# GPRS.net
KiCad netlist of a schematic drawn in Altium Designer
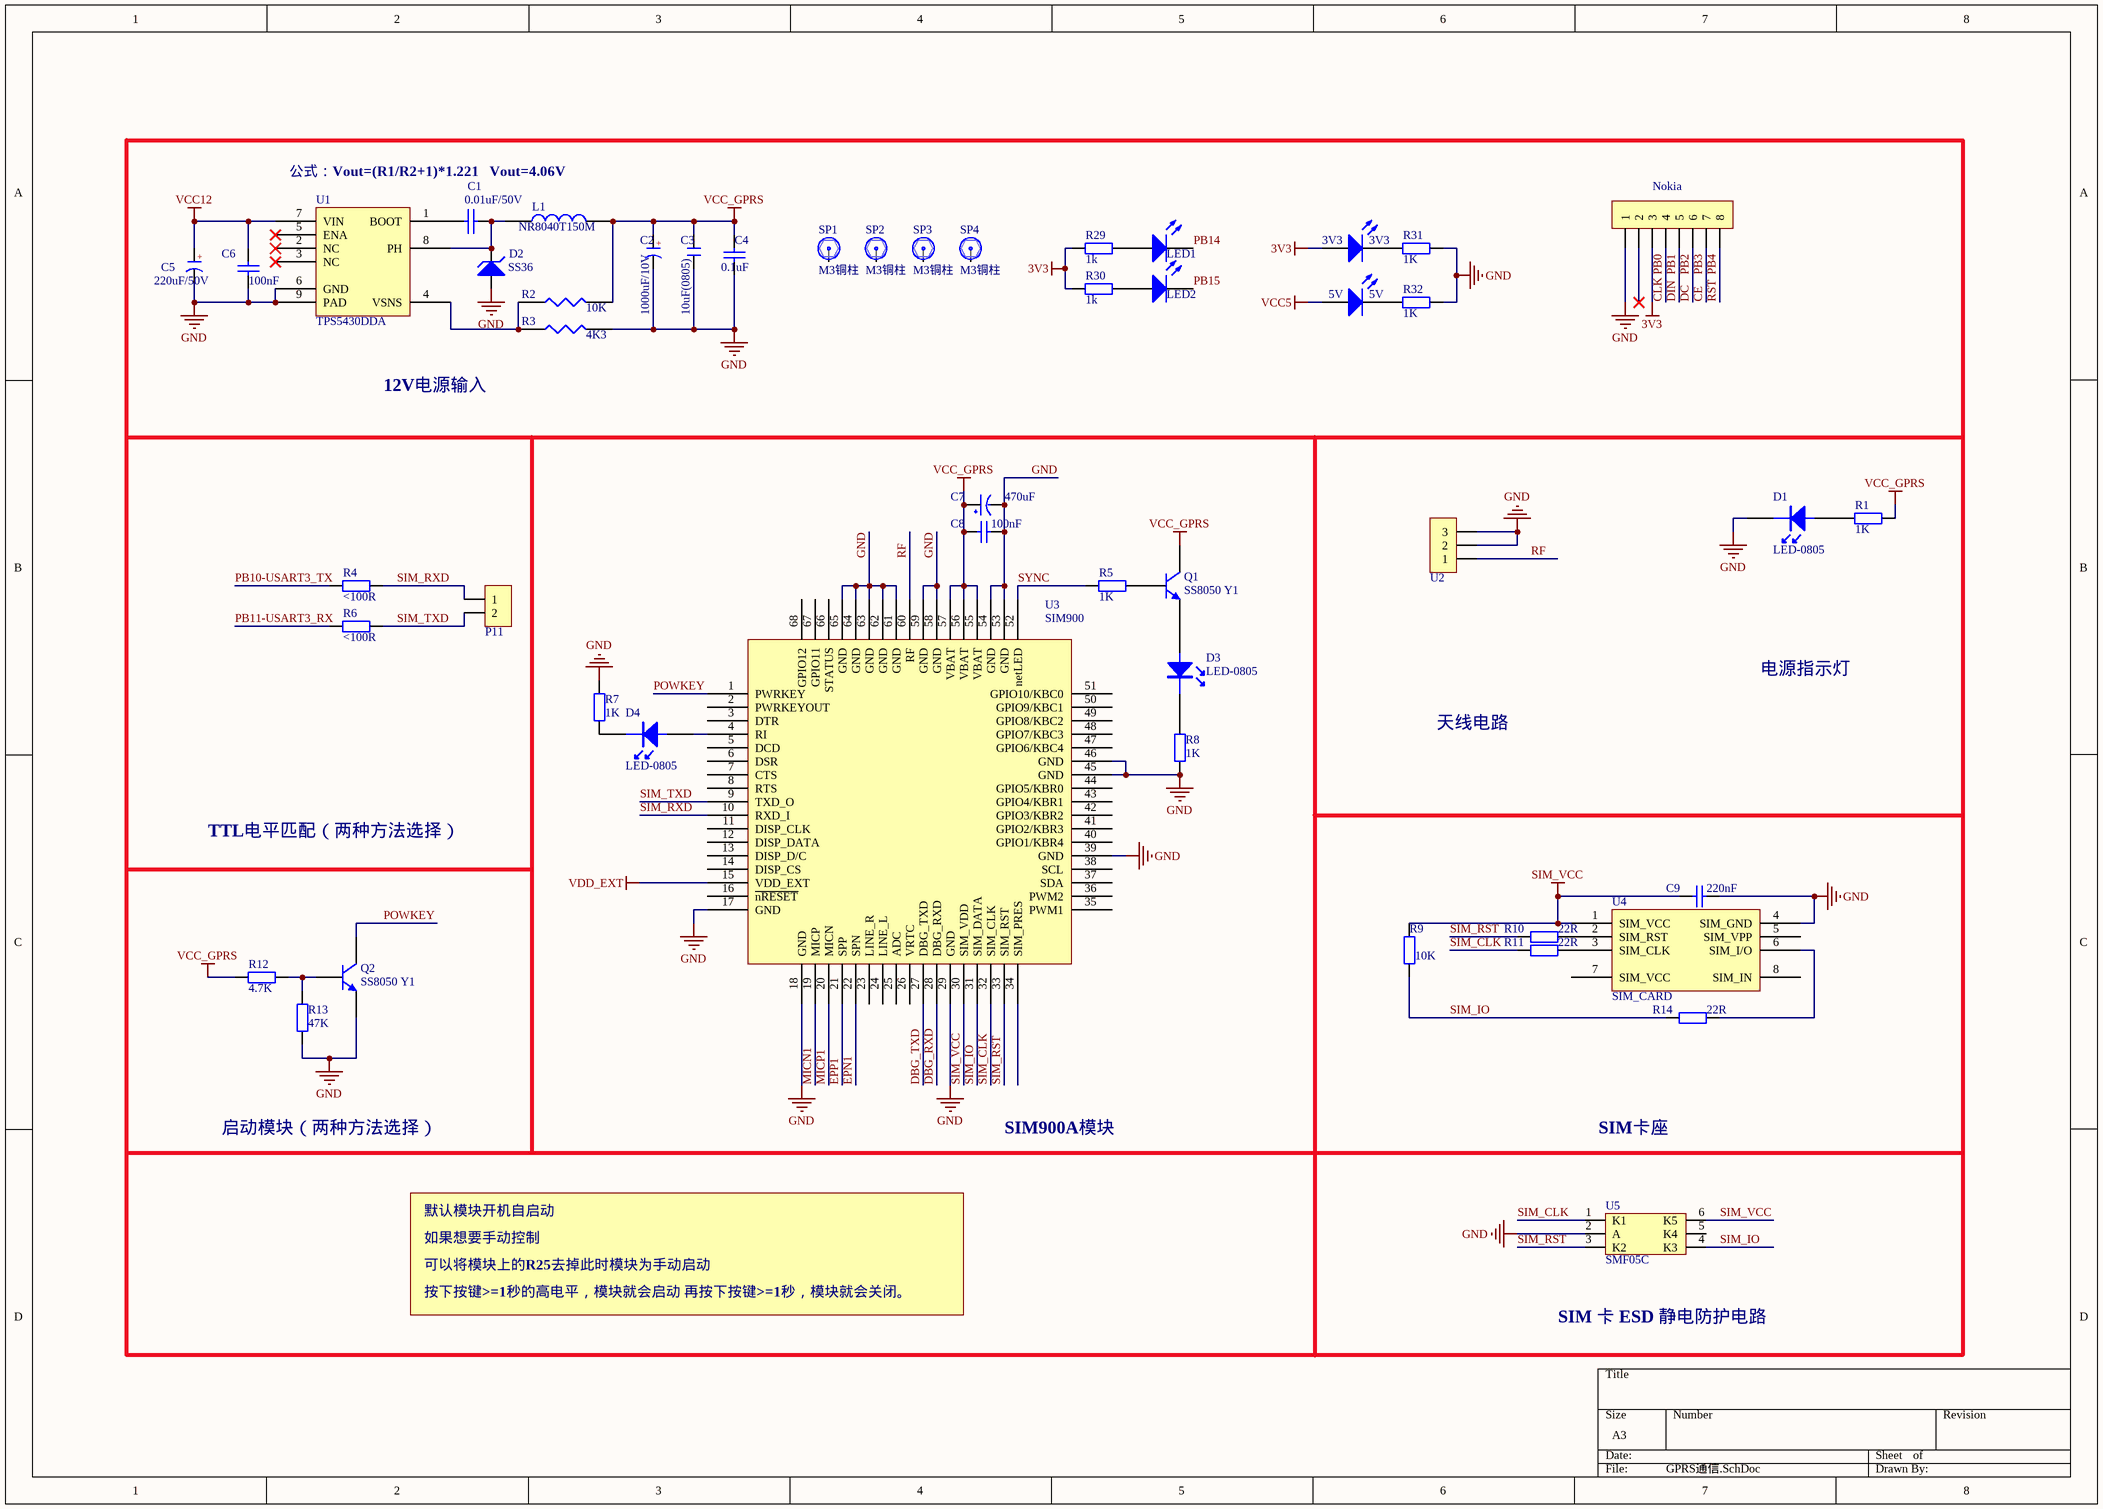
[diagram p0: GPRS通信.SchDoc]

(export (version "E")
  (design (tool "Eeschema 10.0.6"))
  (components
    (comp (ref "3V3")
      (value "3V3")
      (footprint "LED 0805G")
      (description "Typical INFRARED GaAs LED")
      (fields (field (name "PUBLISHER") "Altium Limited"))
      (libsource (lib "PCB_Project") (part "LED0"))
    )
    (comp (ref "5V")
      (value "5V")
      (footprint "LED 0805G")
      (description "Typical INFRARED GaAs LED")
      (fields (field (name "PUBLISHER") "Altium Limited"))
      (libsource (lib "PCB_Project") (part "LED0"))
    )
    (comp (ref "C1")
      (value "0.01uF/50V")
      (footprint "LC-0603_C")
      (description "Capacitor")
      (libsource (lib "*") (part "CAP"))
    )
    (comp (ref "C2")
      (value "1000uF/10V")
      (footprint "CAP 5.0*10*20 - BK")
      (description "直插电解电容")
      (fields (field (name "版权归属") "源创客"))
      (libsource (lib "3.1   - 电阻-电容-电感") (part "C-CAP"))
    )
    (comp (ref "C3")
      (value "10uF(0805)")
      (footprint "C 0805_L")
      (description "无极性贴片电容")
      (fields (field (name "版权归属") "源创客"))
      (libsource (lib "3.1   - 电阻-电容-电感") (part "C"))
    )
    (comp (ref "C4")
      (value "0.1uF")
      (footprint "LC-0603_C")
      (description "贴片电容")
      (libsource (lib "Miscellaneous Devices LC") (part "0603 1.0pF (010) 0.25pF 50V"))
    )
    (comp (ref "C5")
      (value "220uF/50V")
      (footprint "CAP 3.5*8*11.5 - BK")
      (description "直插电解电容")
      (fields (field (name "版权归属") "源创客"))
      (libsource (lib "3.1   - 电阻-电容-电感") (part "C-CAP"))
    )
    (comp (ref "C6")
      (value "100nF")
      (footprint "LC-0603_C")
      (description "贴片电容")
      (libsource (lib "Miscellaneous Devices LC") (part "0603 1uF (105) 10% 50V"))
    )
    (comp (ref "C7")
      (value "470uF")
      (footprint "CM E(8*10.2)")
      (libsource (lib "Explorer STM32F407封装库") (part "CAP"))
    )
    (comp (ref "C8")
      (value "100nF")
      (footprint "LC-0603_C")
      (description "贴片电容")
      (libsource (lib "Miscellaneous Devices LC") (part "0603 1uF (105) 10% 50V"))
    )
    (comp (ref "C9")
      (value "220nF")
      (footprint "LC-0603_C")
      (description "贴片电容")
      (libsource (lib "Miscellaneous Devices LC") (part "0603 1uF (105) 10% 50V"))
    )
    (comp (ref "D1")
      (value "LED-0805")
      (footprint "LED 0805G")
      (description "贴片LED")
      (libsource (lib "CD's_LIB_2018") (part "LED_SMD"))
    )
    (comp (ref "D2")
      (value "SS36")
      (footprint "D1812")
      (description "Zener Diode")
      (libsource (lib "*") (part "SS36"))
    )
    (comp (ref "D3")
      (value "LED-0805")
      (footprint "LED 0805G")
      (description "贴片LED")
      (libsource (lib "CD's_LIB_2018") (part "LED_SMD"))
    )
    (comp (ref "D4")
      (value "LED-0805")
      (footprint "LED 0805G")
      (description "贴片LED")
      (libsource (lib "CD's_LIB_2018") (part "LED_SMD"))
    )
    (comp (ref "L1") (value "NR8040T150M") (footprint "NR8040") (libsource (lib "*") (part "INDUCTOR")))
    (comp (ref "LED1")
      (value "~")
      (footprint "LED 0805G")
      (description "Typical INFRARED GaAs LED")
      (fields (field (name "PUBLISHER") "Altium Limited"))
      (libsource (lib "PCB_Project") (part "LED0"))
    )
    (comp (ref "LED2")
      (value "~")
      (footprint "LED 0805G")
      (description "Typical INFRARED GaAs LED")
      (fields (field (name "PUBLISHER") "Altium Limited"))
      (libsource (lib "PCB_Project") (part "LED0"))
    )
    (comp (ref "Nokia")
      (value "HDR-1X8")
      (footprint "HDR2.54-M-LI-8P")
      (description "8P接插件")
      (fields (field (name "版权归属") "源创客"))
      (libsource (lib "4.5   - 接插件-脚距2.54") (part "Header 8"))
    )
    (comp (ref "P11")
      (value "HDR-1X2")
      (footprint "HDR2.54-LI-2P")
      (description "2P接插件")
      (fields (field (name "版权归属") "源创客"))
      (libsource (lib "4.5   - 接插件-脚距2.54") (part "Header 2"))
    )
    (comp (ref "Q1")
      (value "SS8050 Y1")
      (footprint "LC-SOT-23(SOT-23-3)")
      (description "三极管")
      (libsource (lib "Miscellaneous Devices LC") (part "SOT-23 SS8050 Y1"))
    )
    (comp (ref "Q2")
      (value "SS8050 Y1")
      (footprint "LC-SOT-23(SOT-23-3)")
      (description "三极管")
      (libsource (lib "Miscellaneous Devices LC") (part "SOT-23 SS8050 Y1"))
    )
    (comp (ref "R1")
      (value "1K")
      (footprint "LC-0603_R")
      (description "贴片电阻")
      (libsource (lib "") (part "0603 2KΩ (2001) 1%_1"))
    )
    (comp (ref "R2") (value "10K") (footprint "LC-0603_R") (libsource (lib "*") (part "RES1")))
    (comp (ref "R3") (value "4K3") (footprint "LC-0603_R") (libsource (lib "*") (part "RES1")))
    (comp (ref "R4")
      (value "<100R")
      (footprint "LC-0603_R")
      (description "贴片电阻")
      (libsource (lib "Miscellaneous Devices LC") (part "0603 2KΩ (2001) 1%"))
    )
    (comp (ref "R5")
      (value "1K")
      (footprint "LC-0603_R")
      (description "贴片电阻")
      (libsource (lib "") (part "0603 2KΩ (2001) 1%_1"))
    )
    (comp (ref "R6")
      (value "<100R")
      (footprint "LC-0603_R")
      (description "贴片电阻")
      (libsource (lib "Miscellaneous Devices LC") (part "0603 2KΩ (2001) 1%"))
    )
    (comp (ref "R7")
      (value "1K")
      (footprint "LC-0603_R")
      (description "贴片电阻")
      (libsource (lib "") (part "0603 2KΩ (2001) 1%_2"))
    )
    (comp (ref "R8")
      (value "1K")
      (footprint "LC-0603_R")
      (description "贴片电阻")
      (libsource (lib "") (part "0603 2KΩ (2001) 1%_3"))
    )
    (comp (ref "R9")
      (value "10K")
      (footprint "LC-0603_R")
      (description "贴片电阻")
      (libsource (lib "") (part "0603 2KΩ (2001) 1%_2"))
    )
    (comp (ref "R10")
      (value "22R")
      (footprint "LC-0603_R")
      (description "贴片电阻")
      (libsource (lib "") (part "0603 2KΩ (2001) 1%_1"))
    )
    (comp (ref "R11")
      (value "22R")
      (footprint "LC-0603_R")
      (description "贴片电阻")
      (libsource (lib "") (part "0603 2KΩ (2001) 1%_1"))
    )
    (comp (ref "R12")
      (value "4.7K")
      (footprint "LC-0603_R")
      (description "贴片电阻")
      (libsource (lib "Miscellaneous Devices LC") (part "0603 2KΩ (2001) 1%"))
    )
    (comp (ref "R13")
      (value "47K")
      (footprint "LC-0603_R")
      (description "贴片电阻")
      (libsource (lib "") (part "0603 2KΩ (2001) 1%_2"))
    )
    (comp (ref "R14")
      (value "22R")
      (footprint "LC-0603_R")
      (description "贴片电阻")
      (libsource (lib "") (part "0603 2KΩ (2001) 1%_1"))
    )
    (comp (ref "R29")
      (value "1k")
      (footprint "LC-0603_R")
      (description "贴片电阻")
      (fields (field (name "PUBLISHER") "Altium Limited"))
      (libsource (lib "liu_2016") (part "Res1"))
    )
    (comp (ref "R30")
      (value "1k")
      (footprint "LC-0603_R")
      (description "贴片电阻")
      (fields (field (name "PUBLISHER") "Altium Limited"))
      (libsource (lib "liu_2016") (part "Res1"))
    )
    (comp (ref "R31")
      (value "1K")
      (footprint "LC-0603_R")
      (description "贴片电阻")
      (libsource (lib "Miscellaneous Devices LC") (part "0603 1.1KΩ (1101) 1%"))
    )
    (comp (ref "R32")
      (value "1K")
      (footprint "LC-0603_R")
      (description "贴片电阻")
      (libsource (lib "Miscellaneous Devices LC") (part "0603 1.1KΩ (1101) 1%"))
    )
    (comp (ref "SP1")
      (value "M3铜柱")
      (footprint "M3x10+6_N")
      (description "铜柱")
      (fields (field (name "版权归属") "源创客"))
      (libsource (lib "15.1 - 未分类器件") (part "铜柱加头大焊盘"))
    )
    (comp (ref "SP2")
      (value "M3铜柱")
      (footprint "M3x10+6_N")
      (description "铜柱")
      (fields (field (name "版权归属") "源创客"))
      (libsource (lib "15.1 - 未分类器件") (part "铜柱加头大焊盘"))
    )
    (comp (ref "SP3")
      (value "M3铜柱")
      (footprint "M3x10+6_N")
      (description "铜柱")
      (fields (field (name "版权归属") "源创客"))
      (libsource (lib "15.1 - 未分类器件") (part "铜柱加头大焊盘"))
    )
    (comp (ref "SP4")
      (value "M3铜柱")
      (footprint "M3x10+6_N")
      (description "铜柱")
      (fields (field (name "版权归属") "源创客"))
      (libsource (lib "15.1 - 未分类器件") (part "铜柱加头大焊盘"))
    )
    (comp (ref "U1") (value "TPS5430DDA") (footprint "SO-G8") (libsource (lib "*") (part "TPS5430DDA")))
    (comp (ref "U2")
      (value "HDR-1X3")
      (footprint "SMA-KE-LI")
      (description "3P接插件")
      (fields (field (name "版权归属") "源创客"))
      (libsource (lib "4.5   - 接插件-脚距2.54") (part "Header 3"))
    )
    (comp (ref "U3") (value "SIM900") (footprint "GSM_900A") (libsource (lib "ATK-SIM900A") (part "SIM900")))
    (comp (ref "U4")
      (value "SIM_CARD")
      (footprint "MICRO SIM6")
      (description "SIM中卡卡槽")
      (libsource (lib "liu_2016") (part "SIM_CARD"))
    )
    (comp (ref "U5")
      (value "SMF05C")
      (footprint "SOT-363")
      (description "TVS")
      (libsource (lib "ATK-SIM900A GSM模块封装库") (part "SMF05C"))
    )
  )
  (nets
    (net (code "1") (name "/CE") (class "Default")
      (node (ref "Nokia") (pin "7") (pinfunction "7_7") (pintype "passive"))
    )
    (net (code "2") (name "/CLK") (class "Default")
      (node (ref "Nokia") (pin "4") (pinfunction "4_4") (pintype "passive"))
    )
    (net (code "3") (name "/DBG_RXD") (class "Default")
      (node (ref "U3") (pin "28") (pinfunction "DBG_RXD_28") (pintype "passive"))
    )
    (net (code "4") (name "/DBG_TXD") (class "Default")
      (node (ref "U3") (pin "27") (pinfunction "DBG_TXD_27") (pintype "passive"))
    )
    (net (code "5") (name "/DC") (class "Default")
      (node (ref "Nokia") (pin "6") (pinfunction "6_6") (pintype "passive"))
    )
    (net (code "6") (name "/DIN") (class "Default")
      (node (ref "Nokia") (pin "5") (pinfunction "5_5") (pintype "passive"))
    )
    (net (code "7") (name "/EPN1") (class "Default")
      (node (ref "U3") (pin "22") (pinfunction "SPN_22") (pintype "passive"))
    )
    (net (code "8") (name "/EPP1") (class "Default")
      (node (ref "U3") (pin "21") (pinfunction "SPP_21") (pintype "passive"))
    )
    (net (code "9") (name "/MICN1") (class "Default")
      (node (ref "U3") (pin "19") (pinfunction "MICP_19") (pintype "passive"))
    )
    (net (code "10") (name "/MICP1") (class "Default")
      (node (ref "U3") (pin "20") (pinfunction "MICN_20") (pintype "passive"))
    )
    (net (code "11") (name "/PB4") (class "Default")
      (node (ref "Nokia") (pin "8") (pinfunction "8_8") (pintype "passive"))
    )
    (net (code "12") (name "/PB10-USART3_TX") (class "Default")
      (node (ref "R4") (pin "1") (pinfunction "1_1") (pintype "passive"))
    )
    (net (code "13") (name "/PB11-USART3_RX") (class "Default")
      (node (ref "R6") (pin "1") (pinfunction "1_1") (pintype "passive"))
    )
    (net (code "14") (name "/PB14") (class "Default")
      (node (ref "LED1") (pin "2") (pinfunction "K_2") (pintype "passive"))
    )
    (net (code "15") (name "/PB15") (class "Default")
      (node (ref "LED2") (pin "2") (pinfunction "K_2") (pintype "passive"))
    )
    (net (code "16") (name "/POWKEY") (class "Default")
      (node (ref "Q2") (pin "3") (pinfunction "C_3") (pintype "passive"))
      (node (ref "U3") (pin "1") (pinfunction "PWRKEY_1") (pintype "passive"))
    )
    (net (code "17") (name "/RF") (class "Default")
      (node (ref "U2") (pin "1") (pinfunction "1_1") (pintype "passive"))
      (node (ref "U3") (pin "60") (pinfunction "RF_60") (pintype "passive"))
    )
    (net (code "18") (name "/SIM_CLK") (class "Default")
      (node (ref "R11") (pin "2") (pinfunction "2_2") (pintype "passive"))
      (node (ref "U3") (pin "32") (pinfunction "SIM_CLK_32") (pintype "passive"))
      (node (ref "U5") (pin "1") (pinfunction "K1_1") (pintype "passive"))
    )
    (net (code "19") (name "/SIM_IO") (class "Default")
      (node (ref "R14") (pin "2") (pinfunction "2_2") (pintype "passive"))
      (node (ref "R9") (pin "1") (pinfunction "1_1") (pintype "passive"))
      (node (ref "U3") (pin "31") (pinfunction "SIM_DATA_31") (pintype "passive"))
      (node (ref "U5") (pin "4") (pinfunction "K3_4") (pintype "passive"))
    )
    (net (code "20") (name "/SIM_RST") (class "Default")
      (node (ref "R10") (pin "2") (pinfunction "2_2") (pintype "passive"))
      (node (ref "U3") (pin "33") (pinfunction "SIM_RST_33") (pintype "passive"))
      (node (ref "U5") (pin "3") (pinfunction "K2_3") (pintype "passive"))
    )
    (net (code "21") (name "/SIM_RXD") (class "Default")
      (node (ref "P11") (pin "1") (pinfunction "1_1") (pintype "passive"))
      (node (ref "R4") (pin "2") (pinfunction "2_2") (pintype "passive"))
      (node (ref "U3") (pin "10") (pinfunction "RXD_I_10") (pintype "passive"))
    )
    (net (code "22") (name "/SIM_TXD") (class "Default")
      (node (ref "P11") (pin "2") (pinfunction "2_2") (pintype "passive"))
      (node (ref "R6") (pin "2") (pinfunction "2_2") (pintype "passive"))
      (node (ref "U3") (pin "9") (pinfunction "TXD_O_9") (pintype "passive"))
    )
    (net (code "23") (name "/SYNC") (class "Default")
      (node (ref "R5") (pin "2") (pinfunction "2_2") (pintype "passive"))
      (node (ref "U3") (pin "52") (pinfunction "netLED_52") (pintype "passive"))
    )
    (net (code "24") (name "3V3") (class "Default")
      (node (ref "3V3") (pin "1") (pinfunction "A_1") (pintype "passive"))
      (node (ref "Nokia") (pin "3") (pinfunction "3_3") (pintype "passive"))
      (node (ref "R29") (pin "1") (pinfunction "1_1") (pintype "passive"))
      (node (ref "R30") (pin "1") (pinfunction "1_1") (pintype "passive"))
    )
    (net (code "25") (name "GND") (class "Default")
      (node (ref "C2") (pin "2") (pinfunction "K_2") (pintype "passive"))
      (node (ref "C3") (pin "1") (pinfunction "1_1") (pintype "passive"))
      (node (ref "C4") (pin "1") (pinfunction "1_1") (pintype "passive"))
      (node (ref "C5") (pin "2") (pinfunction "K_2") (pintype "passive"))
      (node (ref "C6") (pin "2") (pinfunction "2_2") (pintype "passive"))
      (node (ref "C7") (pin "2") (pinfunction "GND_2") (pintype "passive"))
      (node (ref "C8") (pin "2") (pinfunction "2_2") (pintype "passive"))
      (node (ref "C9") (pin "2") (pinfunction "2_2") (pintype "passive"))
      (node (ref "D1") (pin "1") (pinfunction "-_1") (pintype "passive"))
      (node (ref "D2") (pin "1") (pinfunction "A_1") (pintype "passive"))
      (node (ref "Nokia") (pin "1") (pinfunction "1_1") (pintype "passive"))
      (node (ref "Q2") (pin "2") (pinfunction "E_2") (pintype "passive"))
      (node (ref "R13") (pin "1") (pinfunction "1_1") (pintype "passive"))
      (node (ref "R3") (pin "2") (pinfunction "2_2") (pintype "passive"))
      (node (ref "R31") (pin "1") (pinfunction "1_1") (pintype "passive"))
      (node (ref "R32") (pin "1") (pinfunction "1_1") (pintype "passive"))
      (node (ref "R7") (pin "2") (pinfunction "2_2") (pintype "passive"))
      (node (ref "R8") (pin "2") (pinfunction "2_2") (pintype "passive"))
      (node (ref "U1") (pin "6") (pinfunction "GND_6") (pintype "passive"))
      (node (ref "U1") (pin "9") (pinfunction "PAD_9") (pintype "passive"))
      (node (ref "U2") (pin "2") (pinfunction "2_2") (pintype "passive"))
      (node (ref "U2") (pin "3") (pinfunction "3_3") (pintype "passive"))
      (node (ref "U3") (pin "17") (pinfunction "GND_17") (pintype "passive"))
      (node (ref "U3") (pin "18") (pinfunction "GND_18") (pintype "passive"))
      (node (ref "U3") (pin "29") (pinfunction "GND_29") (pintype "passive"))
      (node (ref "U3") (pin "39") (pinfunction "GND_39") (pintype "passive"))
      (node (ref "U3") (pin "45") (pinfunction "GND_45") (pintype "passive"))
      (node (ref "U3") (pin "46") (pinfunction "GND_46") (pintype "passive"))
      (node (ref "U3") (pin "53") (pinfunction "GND_53") (pintype "passive"))
      (node (ref "U3") (pin "54") (pinfunction "GND_54") (pintype "passive"))
      (node (ref "U3") (pin "58") (pinfunction "GND_58") (pintype "passive"))
      (node (ref "U3") (pin "59") (pinfunction "GND_59") (pintype "passive"))
      (node (ref "U3") (pin "61") (pinfunction "GND_61") (pintype "passive"))
      (node (ref "U3") (pin "62") (pinfunction "GND_62") (pintype "passive"))
      (node (ref "U3") (pin "63") (pinfunction "GND_63") (pintype "passive"))
      (node (ref "U3") (pin "64") (pinfunction "GND_64") (pintype "passive"))
      (node (ref "U3") (pin "65") (pinfunction "GND_65") (pintype "passive"))
      (node (ref "U4") (pin "4") (pinfunction "SIM_GND_4") (pintype "passive"))
      (node (ref "U5") (pin "2") (pinfunction "A_2") (pintype "passive"))
    )
    (net (code "26") (name "Net-(3V3-K)") (class "Default")
      (node (ref "3V3") (pin "2") (pinfunction "K_2") (pintype "passive"))
      (node (ref "R31") (pin "2") (pinfunction "2_2") (pintype "passive"))
    )
    (net (code "27") (name "Net-(5V-K)") (class "Default")
      (node (ref "5V") (pin "2") (pinfunction "K_2") (pintype "passive"))
      (node (ref "R32") (pin "2") (pinfunction "2_2") (pintype "passive"))
    )
    (net (code "28") (name "Net-(D1-+)") (class "Default")
      (node (ref "D1") (pin "2") (pinfunction "+_2") (pintype "passive"))
      (node (ref "R1") (pin "2") (pinfunction "2_2") (pintype "passive"))
    )
    (net (code "29") (name "Net-(D2-K)") (class "Default")
      (node (ref "C1") (pin "2") (pinfunction "2_2") (pintype "passive"))
      (node (ref "D2") (pin "2") (pinfunction "K_2") (pintype "passive"))
      (node (ref "L1") (pin "1") (pinfunction "1_1") (pintype "passive"))
      (node (ref "U1") (pin "8") (pinfunction "PH_8") (pintype "passive"))
    )
    (net (code "30") (name "Net-(D3-+)") (class "Default")
      (node (ref "D3") (pin "2") (pinfunction "+_2") (pintype "passive"))
      (node (ref "Q1") (pin "2") (pinfunction "E_2") (pintype "passive"))
    )
    (net (code "31") (name "Net-(D3--)") (class "Default")
      (node (ref "D3") (pin "1") (pinfunction "-_1") (pintype "passive"))
      (node (ref "R8") (pin "1") (pinfunction "1_1") (pintype "passive"))
    )
    (net (code "32") (name "Net-(D4-+)") (class "Default")
      (node (ref "D4") (pin "2") (pinfunction "+_2") (pintype "passive"))
      (node (ref "U3") (pin "4") (pinfunction "RI_4") (pintype "passive"))
    )
    (net (code "33") (name "Net-(D4--)") (class "Default")
      (node (ref "D4") (pin "1") (pinfunction "-_1") (pintype "passive"))
      (node (ref "R7") (pin "1") (pinfunction "1_1") (pintype "passive"))
    )
    (net (code "34") (name "Net-(LED1-A)") (class "Default")
      (node (ref "LED1") (pin "1") (pinfunction "A_1") (pintype "passive"))
      (node (ref "R29") (pin "2") (pinfunction "2_2") (pintype "passive"))
    )
    (net (code "35") (name "Net-(LED2-A)") (class "Default")
      (node (ref "LED2") (pin "1") (pinfunction "A_1") (pintype "passive"))
      (node (ref "R30") (pin "2") (pinfunction "2_2") (pintype "passive"))
    )
    (net (code "36") (name "Net-(Q1-B)") (class "Default")
      (node (ref "Q1") (pin "1") (pinfunction "B_1") (pintype "passive"))
      (node (ref "R5") (pin "1") (pinfunction "1_1") (pintype "passive"))
    )
    (net (code "37") (name "Net-(Q2-B)") (class "Default")
      (node (ref "Q2") (pin "1") (pinfunction "B_1") (pintype "passive"))
      (node (ref "R12") (pin "2") (pinfunction "2_2") (pintype "passive"))
      (node (ref "R13") (pin "2") (pinfunction "2_2") (pintype "passive"))
    )
    (net (code "38") (name "Net-(U1-BOOT)") (class "Default")
      (node (ref "C1") (pin "1") (pinfunction "1_1") (pintype "passive"))
      (node (ref "U1") (pin "1") (pinfunction "BOOT_1") (pintype "passive"))
    )
    (net (code "39") (name "Net-(U1-VSNS)") (class "Default")
      (node (ref "R2") (pin "1") (pinfunction "1_1") (pintype "passive"))
      (node (ref "R3") (pin "1") (pinfunction "1_1") (pintype "passive"))
      (node (ref "U1") (pin "4") (pinfunction "VSNS_4") (pintype "passive"))
    )
    (net (code "40") (name "Net-(U4-SIM_CLK)") (class "Default")
      (node (ref "R11") (pin "1") (pinfunction "1_1") (pintype "passive"))
      (node (ref "U4") (pin "3") (pinfunction "SIM_CLK_3") (pintype "passive"))
    )
    (net (code "41") (name "Net-(U4-SIM_I{slash}O)") (class "Default")
      (node (ref "R14") (pin "1") (pinfunction "1_1") (pintype "passive"))
      (node (ref "U4") (pin "6") (pinfunction "SIM_I/O_6") (pintype "passive"))
    )
    (net (code "42") (name "Net-(U4-SIM_RST)") (class "Default")
      (node (ref "R10") (pin "1") (pinfunction "1_1") (pintype "passive"))
      (node (ref "U4") (pin "2") (pinfunction "SIM_RST_2") (pintype "passive"))
    )
    (net (code "43") (name "SIM_VCC") (class "Default")
      (node (ref "C9") (pin "1") (pinfunction "1_1") (pintype "passive"))
      (node (ref "R9") (pin "2") (pinfunction "2_2") (pintype "passive"))
      (node (ref "U3") (pin "30") (pinfunction "SIM_VDD_30") (pintype "passive"))
      (node (ref "U4") (pin "1") (pinfunction "SIM_VCC_1") (pintype "passive"))
      (node (ref "U5") (pin "6") (pinfunction "K5_6") (pintype "passive"))
    )
    (net (code "44") (name "VCC5") (class "Default")
      (node (ref "5V") (pin "1") (pinfunction "A_1") (pintype "passive"))
    )
    (net (code "45") (name "VCC12") (class "Default")
      (node (ref "C5") (pin "1") (pinfunction "A_1") (pintype "passive"))
      (node (ref "C6") (pin "1") (pinfunction "1_1") (pintype "passive"))
      (node (ref "U1") (pin "7") (pinfunction "VIN_7") (pintype "passive"))
    )
    (net (code "46") (name "VCC_GPRS") (class "Default")
      (node (ref "C2") (pin "1") (pinfunction "A_1") (pintype "passive"))
      (node (ref "C3") (pin "2") (pinfunction "2_2") (pintype "passive"))
      (node (ref "C4") (pin "2") (pinfunction "2_2") (pintype "passive"))
      (node (ref "C7") (pin "1") (pinfunction "VCC_1") (pintype "passive"))
      (node (ref "C8") (pin "1") (pinfunction "1_1") (pintype "passive"))
      (node (ref "L1") (pin "2") (pinfunction "2_2") (pintype "passive"))
      (node (ref "Q1") (pin "3") (pinfunction "C_3") (pintype "passive"))
      (node (ref "R1") (pin "1") (pinfunction "1_1") (pintype "passive"))
      (node (ref "R12") (pin "1") (pinfunction "1_1") (pintype "passive"))
      (node (ref "R2") (pin "2") (pinfunction "2_2") (pintype "passive"))
      (node (ref "U3") (pin "55") (pinfunction "VBAT_55") (pintype "passive"))
      (node (ref "U3") (pin "56") (pinfunction "VBAT_56") (pintype "passive"))
      (node (ref "U3") (pin "57") (pinfunction "VBAT_57") (pintype "passive"))
    )
    (net (code "47") (name "VDD_EXT") (class "Default")
      (node (ref "U3") (pin "15") (pinfunction "VDD_EXT_15") (pintype "passive"))
    )
    (net (code "48") (name "unconnected-(Nokia-Pad2)") (class "Default")
      (node (ref "Nokia") (pin "2") (pinfunction "2_2") (pintype "passive+no_connect"))
    )
    (net (code "49") (name "unconnected-(SP1-Pad1)") (class "Default")
      (node (ref "SP1") (pin "1") (pinfunction "1_1") (pintype "passive"))
    )
    (net (code "50") (name "unconnected-(SP2-Pad1)") (class "Default")
      (node (ref "SP2") (pin "1") (pinfunction "1_1") (pintype "passive"))
    )
    (net (code "51") (name "unconnected-(SP3-Pad1)") (class "Default")
      (node (ref "SP3") (pin "1") (pinfunction "1_1") (pintype "passive"))
    )
    (net (code "52") (name "unconnected-(SP4-Pad1)") (class "Default")
      (node (ref "SP4") (pin "1") (pinfunction "1_1") (pintype "passive"))
    )
    (net (code "53") (name "unconnected-(U1-ENA-Pad5)") (class "Default")
      (node (ref "U1") (pin "5") (pinfunction "ENA_5") (pintype "passive+no_connect"))
    )
    (net (code "54") (name "unconnected-(U1-NC-Pad2)") (class "Default")
      (node (ref "U1") (pin "2") (pinfunction "NC_2") (pintype "passive+no_connect"))
    )
    (net (code "55") (name "unconnected-(U1-NC-Pad3)") (class "Default")
      (node (ref "U1") (pin "3") (pinfunction "NC_3") (pintype "passive+no_connect"))
    )
    (net (code "56") (name "unconnected-(U3-ADC-Pad25)") (class "Default")
      (node (ref "U3") (pin "25") (pinfunction "ADC_25") (pintype "passive"))
    )
    (net (code "57") (name "unconnected-(U3-CTS-Pad7)") (class "Default")
      (node (ref "U3") (pin "7") (pinfunction "CTS_7") (pintype "passive"))
    )
    (net (code "58") (name "unconnected-(U3-DCD-Pad5)") (class "Default")
      (node (ref "U3") (pin "5") (pinfunction "DCD_5") (pintype "passive"))
    )
    (net (code "59") (name "unconnected-(U3-DISP_CLK-Pad11)") (class "Default")
      (node (ref "U3") (pin "11") (pinfunction "DISP_CLK_11") (pintype "passive"))
    )
    (net (code "60") (name "unconnected-(U3-DISP_CS-Pad14)") (class "Default")
      (node (ref "U3") (pin "14") (pinfunction "DISP_CS_14") (pintype "passive"))
    )
    (net (code "61") (name "unconnected-(U3-DISP_DATA-Pad12)") (class "Default")
      (node (ref "U3") (pin "12") (pinfunction "DISP_DATA_12") (pintype "passive"))
    )
    (net (code "62") (name "unconnected-(U3-DISP_D{slash}C-Pad13)") (class "Default")
      (node (ref "U3") (pin "13") (pinfunction "DISP_D/C_13") (pintype "passive"))
    )
    (net (code "63") (name "unconnected-(U3-DSR-Pad6)") (class "Default")
      (node (ref "U3") (pin "6") (pinfunction "DSR_6") (pintype "passive"))
    )
    (net (code "64") (name "unconnected-(U3-DTR-Pad3)") (class "Default")
      (node (ref "U3") (pin "3") (pinfunction "DTR_3") (pintype "passive"))
    )
    (net (code "65") (name "unconnected-(U3-GPIO1{slash}KBR4-Pad40)") (class "Default")
      (node (ref "U3") (pin "40") (pinfunction "GPIO1/KBR4_40") (pintype "passive"))
    )
    (net (code "66") (name "unconnected-(U3-GPIO2{slash}KBR3-Pad41)") (class "Default")
      (node (ref "U3") (pin "41") (pinfunction "GPIO2/KBR3_41") (pintype "passive"))
    )
    (net (code "67") (name "unconnected-(U3-GPIO3{slash}KBR2-Pad42)") (class "Default")
      (node (ref "U3") (pin "42") (pinfunction "GPIO3/KBR2_42") (pintype "passive"))
    )
    (net (code "68") (name "unconnected-(U3-GPIO4{slash}KBR1-Pad43)") (class "Default")
      (node (ref "U3") (pin "43") (pinfunction "GPIO4/KBR1_43") (pintype "passive"))
    )
    (net (code "69") (name "unconnected-(U3-GPIO5{slash}KBR0-Pad44)") (class "Default")
      (node (ref "U3") (pin "44") (pinfunction "GPIO5/KBR0_44") (pintype "passive"))
    )
    (net (code "70") (name "unconnected-(U3-GPIO6{slash}KBC4-Pad47)") (class "Default")
      (node (ref "U3") (pin "47") (pinfunction "GPIO6/KBC4_47") (pintype "passive"))
    )
    (net (code "71") (name "unconnected-(U3-GPIO7{slash}KBC3-Pad48)") (class "Default")
      (node (ref "U3") (pin "48") (pinfunction "GPIO7/KBC3_48") (pintype "passive"))
    )
    (net (code "72") (name "unconnected-(U3-GPIO8{slash}KBC2-Pad49)") (class "Default")
      (node (ref "U3") (pin "49") (pinfunction "GPIO8/KBC2_49") (pintype "passive"))
    )
    (net (code "73") (name "unconnected-(U3-GPIO9{slash}KBC1-Pad50)") (class "Default")
      (node (ref "U3") (pin "50") (pinfunction "GPIO9/KBC1_50") (pintype "passive"))
    )
    (net (code "74") (name "unconnected-(U3-GPIO10{slash}KBC0-Pad51)") (class "Default")
      (node (ref "U3") (pin "51") (pinfunction "GPIO10/KBC0_51") (pintype "passive"))
    )
    (net (code "75") (name "unconnected-(U3-GPIO11-Pad67)") (class "Default")
      (node (ref "U3") (pin "67") (pinfunction "GPIO11_67") (pintype "passive"))
    )
    (net (code "76") (name "unconnected-(U3-GPIO12-Pad68)") (class "Default")
      (node (ref "U3") (pin "68") (pinfunction "GPIO12_68") (pintype "passive"))
    )
    (net (code "77") (name "unconnected-(U3-LINE_L-Pad24)") (class "Default")
      (node (ref "U3") (pin "24") (pinfunction "LINE_L_24") (pintype "passive"))
    )
    (net (code "78") (name "unconnected-(U3-LINE_R-Pad23)") (class "Default")
      (node (ref "U3") (pin "23") (pinfunction "LINE_R_23") (pintype "passive"))
    )
    (net (code "79") (name "unconnected-(U3-PWM1-Pad35)") (class "Default")
      (node (ref "U3") (pin "35") (pinfunction "PWM1_35") (pintype "passive"))
    )
    (net (code "80") (name "unconnected-(U3-PWM2-Pad36)") (class "Default")
      (node (ref "U3") (pin "36") (pinfunction "PWM2_36") (pintype "passive"))
    )
    (net (code "81") (name "unconnected-(U3-PWRKEYOUT-Pad2)") (class "Default")
      (node (ref "U3") (pin "2") (pinfunction "PWRKEYOUT_2") (pintype "passive"))
    )
    (net (code "82") (name "unconnected-(U3-RTS-Pad8)") (class "Default")
      (node (ref "U3") (pin "8") (pinfunction "RTS_8") (pintype "passive"))
    )
    (net (code "83") (name "unconnected-(U3-SCL-Pad38)") (class "Default")
      (node (ref "U3") (pin "38") (pinfunction "SCL_38") (pintype "passive"))
    )
    (net (code "84") (name "unconnected-(U3-SDA-Pad37)") (class "Default")
      (node (ref "U3") (pin "37") (pinfunction "SDA_37") (pintype "passive"))
    )
    (net (code "85") (name "unconnected-(U3-SIM_PRES-Pad34)") (class "Default")
      (node (ref "U3") (pin "34") (pinfunction "SIM_PRES_34") (pintype "passive"))
    )
    (net (code "86") (name "unconnected-(U3-STATUS-Pad66)") (class "Default")
      (node (ref "U3") (pin "66") (pinfunction "STATUS_66") (pintype "passive"))
    )
    (net (code "87") (name "unconnected-(U3-VRTC-Pad26)") (class "Default")
      (node (ref "U3") (pin "26") (pinfunction "VRTC_26") (pintype "passive"))
    )
    (net (code "88") (name "unconnected-(U3-~{nRESET}-Pad16)") (class "Default")
      (node (ref "U3") (pin "16") (pinfunction "~{nRESET}_16") (pintype "passive"))
    )
    (net (code "89") (name "unconnected-(U4-SIM_IN-Pad8)") (class "Default")
      (node (ref "U4") (pin "8") (pinfunction "SIM_IN_8") (pintype "passive"))
    )
    (net (code "90") (name "unconnected-(U4-SIM_VCC-Pad7)") (class "Default")
      (node (ref "U4") (pin "7") (pinfunction "SIM_VCC_7") (pintype "passive"))
    )
    (net (code "91") (name "unconnected-(U4-SIM_VPP-Pad5)") (class "Default")
      (node (ref "U4") (pin "5") (pinfunction "SIM_VPP_5") (pintype "passive"))
    )
    (net (code "92") (name "unconnected-(U5-K4-Pad5)") (class "Default")
      (node (ref "U5") (pin "5") (pinfunction "K4_5") (pintype "passive"))
    )
  )
)
